# BUB-III-r1.net
KiCad netlist of a schematic drawn in EAGLE
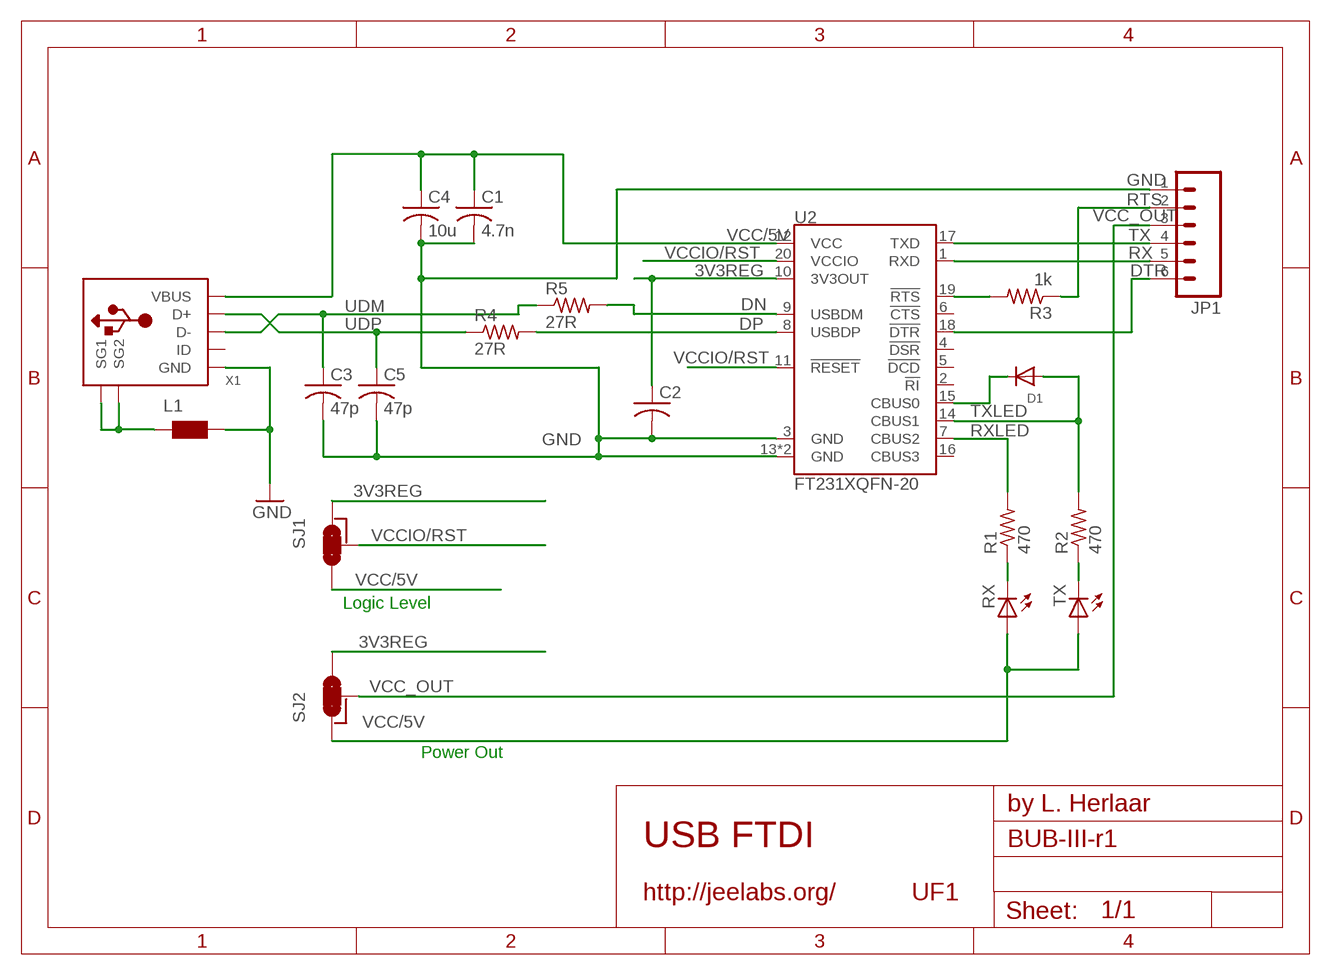
[diagram p0: schematic, sheet 1]

(export (version "E")
  (design (tool "Eeschema 10.0.6"))
  (components
    (comp (ref "C1")
      (value "4.7n")
      (footprint "eagle-import:C0603K")
      (libsource (lib "eagle-import") (part "C-USC0603K"))
    )
    (comp (ref "C2")
      (value "C-USC0603K")
      (footprint "eagle-import:C0603K")
      (libsource (lib "eagle-import") (part "C-USC0603K"))
    )
    (comp (ref "C3")
      (value "47p")
      (footprint "eagle-import:C0603K")
      (libsource (lib "eagle-import") (part "C-USC0603K"))
    )
    (comp (ref "C4")
      (value "10u")
      (footprint "eagle-import:C0805K")
      (libsource (lib "eagle-import") (part "C-USC0805K"))
    )
    (comp (ref "C5")
      (value "47p")
      (footprint "eagle-import:C0603K")
      (libsource (lib "eagle-import") (part "C-USC0603K"))
    )
    (comp (ref "D1")
      (value "DIODE_SOD-323")
      (footprint "eagle-import:SOD-323")
      (libsource (lib "eagle-import") (part "DIODE_SOD-323"))
    )
    (comp (ref "JP1")
      (value "M06SMD-FEMALE-V2")
      (footprint "eagle-import:1X06-SMD-FEMALE-V2")
      (libsource (lib "eagle-import") (part "M06SMD-FEMALE-V2"))
    )
    (comp (ref "L1")
      (value "FERRITE_BEAD_0603")
      (footprint "eagle-import:WUERTH-ELEKTRONIK_0603")
      (libsource (lib "eagle-import") (part "FERRITE_BEAD_0603"))
    )
    (comp (ref "R1")
      (value "470")
      (footprint "eagle-import:R0603")
      (libsource (lib "eagle-import") (part "R-US_R0603"))
    )
    (comp (ref "R2")
      (value "470")
      (footprint "eagle-import:R0603")
      (libsource (lib "eagle-import") (part "R-US_R0603"))
    )
    (comp (ref "R3")
      (value "1k")
      (footprint "eagle-import:R0603")
      (libsource (lib "eagle-import") (part "R-US_R0603"))
    )
    (comp (ref "R4")
      (value "27R")
      (footprint "eagle-import:R0603")
      (libsource (lib "eagle-import") (part "R-US_R0603"))
    )
    (comp (ref "R5")
      (value "27R")
      (footprint "eagle-import:R0603")
      (libsource (lib "eagle-import") (part "R-US_R0603"))
    )
    (comp (ref "RX")
      (value "LEDCHIP-LED0805")
      (footprint "eagle-import:CHIP-LED0805")
      (libsource (lib "eagle-import") (part "LEDCHIP-LED0805"))
    )
    (comp (ref "SJ1")
      (value "SOLDERJUMP_SPDTSHORT_PASTE")
      (footprint "eagle-import:SJ-SHRTINPASTE")
      (libsource (lib "eagle-import") (part "SOLDERJUMP_SPDTSHORT_PASTE"))
    )
    (comp (ref "SJ2")
      (value "SOLDERJUMP_SPDTSHORT_PASTE")
      (footprint "eagle-import:SJ-SHRTINPASTE")
      (libsource (lib "eagle-import") (part "SOLDERJUMP_SPDTSHORT_PASTE"))
    )
    (comp (ref "TX")
      (value "LEDCHIP-LED0805")
      (footprint "eagle-import:CHIP-LED0805")
      (libsource (lib "eagle-import") (part "LEDCHIP-LED0805"))
    )
    (comp (ref "U2")
      (value "FT231XQFN-20")
      (footprint "eagle-import:QFN-20")
      (libsource (lib "eagle-import") (part "FT231XQFN-20"))
    )
    (comp (ref "X1")
      (value "USB")
      (footprint "eagle-import:USB-AB-MICRO-SMD")
      (libsource (lib "eagle-import") (part "USB"))
    )
  )
  (nets
    (net (code "1") (name "/3V3REG") (class "Default")
      (node (ref "C2") (pin "1") (pinfunction "1_1") (pintype "passive"))
      (node (ref "SJ1") (pin "1") (pinfunction "1_1") (pintype "passive"))
      (node (ref "SJ2") (pin "3") (pinfunction "3_3") (pintype "passive"))
      (node (ref "U2") (pin "10") (pinfunction "3V3OUT_10") (pintype "bidirectional"))
    )
    (net (code "2") (name "/DN") (class "Default")
      (node (ref "R5") (pin "2") (pinfunction "2_2") (pintype "passive"))
      (node (ref "U2") (pin "9") (pinfunction "USBDM_9") (pintype "bidirectional"))
    )
    (net (code "3") (name "/DP") (class "Default")
      (node (ref "R4") (pin "2") (pinfunction "2_2") (pintype "passive"))
      (node (ref "U2") (pin "8") (pinfunction "USBDP_8") (pintype "bidirectional"))
    )
    (net (code "4") (name "/DTR") (class "Default")
      (node (ref "JP1") (pin "6") (pinfunction "6_6") (pintype "passive"))
      (node (ref "U2") (pin "18") (pinfunction "~{DTR}_18") (pintype "bidirectional"))
    )
    (net (code "5") (name "/RTS") (class "Default")
      (node (ref "JP1") (pin "2") (pinfunction "2_2") (pintype "passive"))
      (node (ref "R3") (pin "1") (pinfunction "1_1") (pintype "passive"))
    )
    (net (code "6") (name "/RX") (class "Default")
      (node (ref "JP1") (pin "5") (pinfunction "5_5") (pintype "passive"))
      (node (ref "U2") (pin "1") (pinfunction "RXD_1") (pintype "bidirectional"))
    )
    (net (code "7") (name "/RXLED") (class "Default")
      (node (ref "R1") (pin "2") (pinfunction "2_2") (pintype "passive"))
      (node (ref "U2") (pin "7") (pinfunction "CBUS2_7") (pintype "bidirectional"))
    )
    (net (code "8") (name "/TX") (class "Default")
      (node (ref "JP1") (pin "4") (pinfunction "4_4") (pintype "passive"))
      (node (ref "U2") (pin "17") (pinfunction "TXD_17") (pintype "bidirectional"))
    )
    (net (code "9") (name "/TXLED") (class "Default")
      (node (ref "D1") (pin "A") (pinfunction "A_A") (pintype "passive"))
      (node (ref "R2") (pin "2") (pinfunction "2_2") (pintype "passive"))
      (node (ref "U2") (pin "14") (pinfunction "CBUS1_14") (pintype "bidirectional"))
    )
    (net (code "10") (name "/UDM") (class "Default")
      (node (ref "C3") (pin "1") (pinfunction "1_1") (pintype "passive"))
      (node (ref "R5") (pin "1") (pinfunction "1_1") (pintype "passive"))
      (node (ref "X1") (pin "D-") (pinfunction "D-_D-") (pintype "bidirectional"))
    )
    (net (code "11") (name "/UDP") (class "Default")
      (node (ref "C5") (pin "1") (pinfunction "1_1") (pintype "passive"))
      (node (ref "R4") (pin "1") (pinfunction "1_1") (pintype "passive"))
      (node (ref "X1") (pin "D+") (pinfunction "D+_D+") (pintype "bidirectional"))
    )
    (net (code "12") (name "/VCCIO{slash}RST") (class "Default")
      (node (ref "SJ1") (pin "2") (pinfunction "2_2") (pintype "passive"))
      (node (ref "U2") (pin "11") (pinfunction "~{RESET}_11") (pintype "bidirectional"))
      (node (ref "U2") (pin "20") (pinfunction "VCCIO_20") (pintype "bidirectional"))
    )
    (net (code "13") (name "/VCC_OUT") (class "Default")
      (node (ref "JP1") (pin "3") (pinfunction "3_3") (pintype "passive"))
      (node (ref "SJ2") (pin "2") (pinfunction "2_2") (pintype "passive"))
    )
    (net (code "14") (name "/VCC{slash}5V") (class "Default")
      (node (ref "C1") (pin "1") (pinfunction "1_1") (pintype "passive"))
      (node (ref "C4") (pin "1") (pinfunction "1_1") (pintype "passive"))
      (node (ref "RX") (pin "A") (pinfunction "A_A") (pintype "passive"))
      (node (ref "SJ1") (pin "3") (pinfunction "3_3") (pintype "passive"))
      (node (ref "SJ2") (pin "1") (pinfunction "1_1") (pintype "passive"))
      (node (ref "TX") (pin "A") (pinfunction "A_A") (pintype "passive"))
      (node (ref "U2") (pin "12") (pinfunction "VCC_12") (pintype "bidirectional"))
      (node (ref "X1") (pin "VBUS") (pinfunction "VBUS_VBUS") (pintype "power_in"))
    )
    (net (code "15") (name "GND") (class "Default")
      (node (ref "C1") (pin "2") (pinfunction "2_2") (pintype "passive"))
      (node (ref "C2") (pin "2") (pinfunction "2_2") (pintype "passive"))
      (node (ref "C3") (pin "2") (pinfunction "2_2") (pintype "passive"))
      (node (ref "C4") (pin "2") (pinfunction "2_2") (pintype "passive"))
      (node (ref "C5") (pin "2") (pinfunction "2_2") (pintype "passive"))
      (node (ref "JP1") (pin "1") (pinfunction "1_1") (pintype "passive"))
      (node (ref "L1") (pin "2") (pinfunction "2_2") (pintype "passive"))
      (node (ref "U2") (pin "13") (pinfunction "GND_13") (pintype "bidirectional"))
      (node (ref "U2") (pin "3") (pinfunction "GND_3") (pintype "bidirectional"))
      (node (ref "U2") (pin "P") (pinfunction "GND_P") (pintype "bidirectional"))
      (node (ref "X1") (pin "GND") (pinfunction "GND_GND") (pintype "power_in"))
    )
    (net (code "16") (name "Net-(L1-Pad1)") (class "Default")
      (node (ref "L1") (pin "1") (pinfunction "1_1") (pintype "passive"))
      (node (ref "X1") (pin "P$1") (pinfunction "SG1_P$1") (pintype "bidirectional"))
      (node (ref "X1") (pin "P$2") (pinfunction "SG2_P$2") (pintype "bidirectional"))
      (node (ref "X1") (pin "P$3") (pinfunction "SG1_P$3") (pintype "bidirectional"))
      (node (ref "X1") (pin "P$4") (pinfunction "SG2_P$4") (pintype "bidirectional"))
    )
    (net (code "17") (name "Net-(R1-Pad1)") (class "Default")
      (node (ref "R1") (pin "1") (pinfunction "1_1") (pintype "passive"))
      (node (ref "RX") (pin "C") (pinfunction "C_C") (pintype "passive"))
    )
    (net (code "18") (name "Net-(R2-Pad1)") (class "Default")
      (node (ref "R2") (pin "1") (pinfunction "1_1") (pintype "passive"))
      (node (ref "TX") (pin "C") (pinfunction "C_C") (pintype "passive"))
    )
    (net (code "19") (name "Net-(U2-CBUS0)") (class "Default")
      (node (ref "D1") (pin "C") (pinfunction "C_C") (pintype "passive"))
      (node (ref "U2") (pin "15") (pinfunction "CBUS0_15") (pintype "bidirectional"))
    )
    (net (code "20") (name "Net-(U2-~{RTS})") (class "Default")
      (node (ref "R3") (pin "2") (pinfunction "2_2") (pintype "passive"))
      (node (ref "U2") (pin "19") (pinfunction "~{RTS}_19") (pintype "bidirectional"))
    )
    (net (code "21") (name "unconnected-(U2-CBUS3-Pad16)") (class "Default")
      (node (ref "U2") (pin "16") (pinfunction "CBUS3_16") (pintype "bidirectional"))
    )
    (net (code "22") (name "unconnected-(U2-~{CTS}-Pad6)") (class "Default")
      (node (ref "U2") (pin "6") (pinfunction "~{CTS}_6") (pintype "bidirectional"))
    )
    (net (code "23") (name "unconnected-(U2-~{DCD}-Pad5)") (class "Default")
      (node (ref "U2") (pin "5") (pinfunction "~{DCD}_5") (pintype "bidirectional"))
    )
    (net (code "24") (name "unconnected-(U2-~{DSR}-Pad4)") (class "Default")
      (node (ref "U2") (pin "4") (pinfunction "~{DSR}_4") (pintype "bidirectional"))
    )
    (net (code "25") (name "unconnected-(U2-~{RI}-Pad2)") (class "Default")
      (node (ref "U2") (pin "2") (pinfunction "~{RI}_2") (pintype "bidirectional"))
    )
    (net (code "26") (name "unconnected-(X1-PadID)") (class "Default")
      (node (ref "X1") (pin "ID") (pinfunction "ID_ID") (pintype "bidirectional"))
    )
  )
)
